# Power.net
KiCad netlist of a schematic drawn in Altium Designer
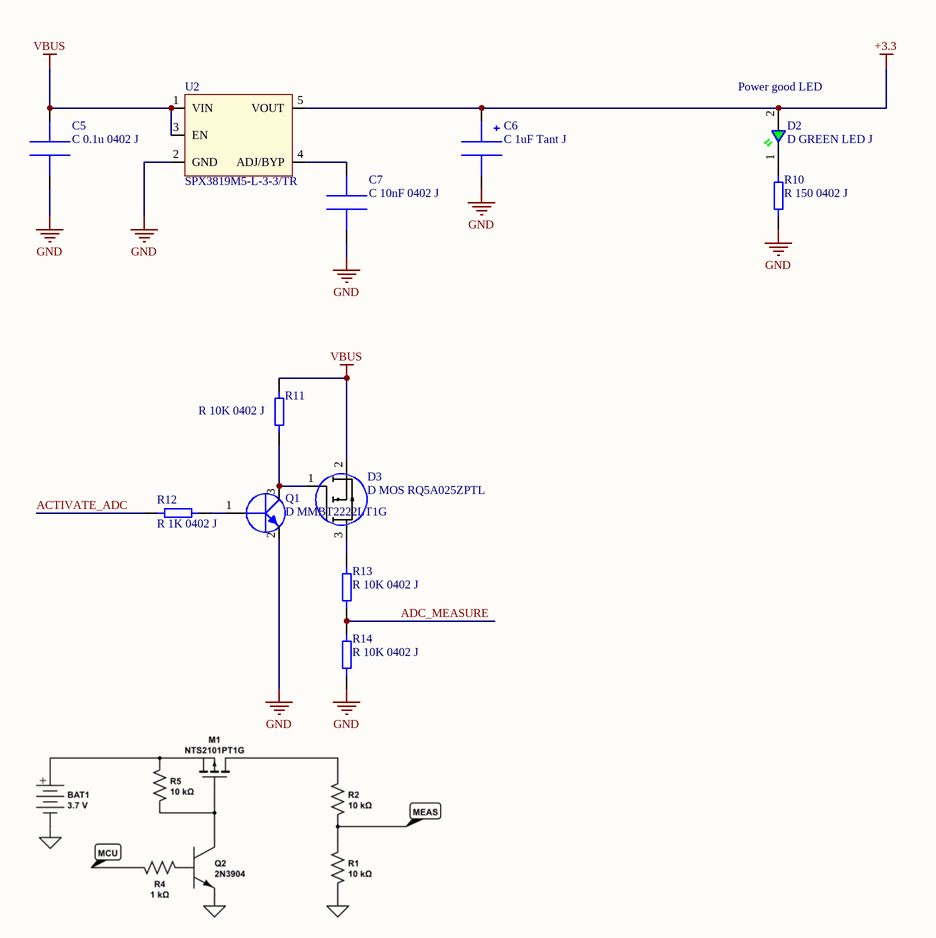
[diagram p0: Power.SchDoc]

(export (version "E")
  (design (tool "Eeschema 10.0.6"))
  (components
    (comp (ref "C5")
      (value "C 0.1u 0402 J")
      (footprint "C0402")
      (description "Cap Ceramic 0.1uF 50V X7R 10% Pad SMD 0402 125C Low ESR Automotive CL05B104KB54PNC")
      (fields
        (field (name "MANUFACTURER") "Samsung")
        (field (name "MANUFACTURER PART NUMBER") "CL05B104KB54PNC")
      )
      (libsource (lib "Schlib1") (part "C 0.1u 0402 J"))
    )
    (comp (ref "C6")
      (value "C 1uF Tant J")
      (footprint "C AVX CAP TANT CASE A")
      (fields
        (field (name "MANUFACTURER") "Kyocera AVX")
        (field (name "MANUFACTURER PART NUMBER") "TAJA105K016RNJ")
        (field (name "TOLERANCE") "20%")
      )
      (libsource (lib "Schlib1") (part "C 1uF Tant J"))
    )
    (comp (ref "C7")
      (value "C 10nF 0402 J")
      (footprint "C0402")
      (description "Ceramic capacitor SMD-0402 10nF /50V X7R# K +-10%, Samsung, RoHS CL05B103KB5NNNC")
      (fields
        (field (name "MANUFACTURER") "Samsung")
        (field (name "MANUFACTURER PART NUMBER") "CL05B103KB5NNNC")
      )
      (libsource (lib "Schlib1") (part "C 10nF 0402 J"))
    )
    (comp (ref "D2")
      (value "D GREEN LED J")
      (footprint "NCD0402C1")
      (description "Green/Yellow-Green 0402 Light Emitting Diodes (LED) ROHS NCD0402C1")
      (fields
        (field (name "MANUFACTURER") "Foshan NationStar Optoelectronics")
        (field (name "MANUFACTURER PART NUMBER") "NCD0402C1")
      )
      (libsource (lib "Schlib1") (part "D GREEN LED J"))
    )
    (comp (ref "D3")
      (value "D MOS RQ5A025ZPTL")
      (footprint "SC96 SOT346T")
      (description "Transistor Mosfet P-ch 12V 2.5A 3-PIN Tsmt T/r")
      (fields (field (name "MANUFACTURER") "Rohm") (field (name "MANUFACTURER PART NUMBER") "RQ5A025ZPTL"))
      (libsource (lib "Schlib1") (part "D MOS RQ5A025ZPTL"))
    )
    (comp (ref "Q1")
      (value "D MMBT2222LT1G")
      (footprint "SOT23")
      (description "Trans GP BJT NPN 30V 0.6A 3-Pin SOT-23 T/R")
      (fields
        (field (name "MANUFACTURER") "ON Semiconductor")
        (field (name "MANUFACTURER PART NUMBER") "MMBT2222LT1G")
      )
      (libsource (lib "Schlib1") (part "D MMBT2222LT1G"))
    )
    (comp (ref "R10")
      (value "R 150 0402 J")
      (footprint "R0402")
      (fields
        (field (name "MANUFACTURER") "Yageo")
        (field (name "MANUFACTURER PART NUMBER") "RC0402FR-07150RL")
        (field (name "TOLERANCE") "1%")
      )
      (libsource (lib "Schlib1") (part "R 150 0402 J"))
    )
    (comp (ref "R11")
      (value "R 10K 0402 J")
      (footprint "R0402")
      (description "Res Thick Film 0402 10K Ohm 1% 0.063W(1/16W) ±100ppm/C Pad SMD Automotive T/R AC0402FR-0710KL")
      (fields
        (field (name "MANUFACTURER") "Yageo")
        (field (name "MANUFACTURER PART NUMBER") "AC0402FR-0710KL")
      )
      (libsource (lib "Schlib1") (part "R 10K 0402 J"))
    )
    (comp (ref "R12")
      (value "R 1K 0402 J")
      (footprint "R0402")
      (description "Res Thick Film 0402 1K Ohm 1% 0.063W(1/16W) ±100ppm/C Pad SMD Automotive T/R")
      (fields
        (field (name "MANUFACTURER") "Yageo")
        (field (name "MANUFACTURER PART NUMBER") "AC0402FR-071KL")
      )
      (libsource (lib "Schlib1") (part "R 1K 0402 J"))
    )
    (comp (ref "R13")
      (value "R 10K 0402 J")
      (footprint "R0402")
      (description "Res Thick Film 0402 10K Ohm 1% 0.063W(1/16W) ±100ppm/C Pad SMD Automotive T/R AC0402FR-0710KL")
      (fields
        (field (name "MANUFACTURER") "Yageo")
        (field (name "MANUFACTURER PART NUMBER") "AC0402FR-0710KL")
      )
      (libsource (lib "Schlib1") (part "R 10K 0402 J"))
    )
    (comp (ref "R14")
      (value "R 10K 0402 J")
      (footprint "R0402")
      (description "Res Thick Film 0402 10K Ohm 1% 0.063W(1/16W) ±100ppm/C Pad SMD Automotive T/R AC0402FR-0710KL")
      (fields
        (field (name "MANUFACTURER") "Yageo")
        (field (name "MANUFACTURER PART NUMBER") "AC0402FR-0710KL")
      )
      (libsource (lib "Schlib1") (part "R 10K 0402 J"))
    )
    (comp (ref "U2")
      (value "SPX3819M5-L-3-3/TR")
      (footprint "SOT23-5")
      (description "SPX3819 Series 3.3 V 500 mA Fixed Output SMT LDO Regulator - SOT-23-5")
      (fields (field (name "MANUFACTURER") "MaxLinear"))
      (libsource (lib "Schlib1") (part "U SPX3819M5 3.3V"))
    )
  )
  (nets
    (net (code "1") (name "+3.3") (class "Default")
      (node (ref "C6") (pin "A") (pinfunction "A_A") (pintype "passive"))
      (node (ref "D2") (pin "2") (pinfunction "2_2") (pintype "passive"))
      (node (ref "U2") (pin "5") (pinfunction "VOUT_5") (pintype "passive"))
    )
    (net (code "2") (name "/ACTIVATE_ADC") (class "Default")
      (node (ref "R12") (pin "1") (pinfunction "1_1") (pintype "passive"))
    )
    (net (code "3") (name "/ADC_MEASURE") (class "Default")
      (node (ref "R13") (pin "1") (pinfunction "1_1") (pintype "passive"))
      (node (ref "R14") (pin "2") (pinfunction "2_2") (pintype "passive"))
    )
    (net (code "4") (name "GND") (class "Default")
      (node (ref "C5") (pin "1") (pinfunction "1_1") (pintype "passive"))
      (node (ref "C6") (pin "K") (pinfunction "K_K") (pintype "passive"))
      (node (ref "C7") (pin "1") (pinfunction "1_1") (pintype "passive"))
      (node (ref "Q1") (pin "2") (pinfunction "2_2") (pintype "passive"))
      (node (ref "R10") (pin "1") (pinfunction "1_1") (pintype "passive"))
      (node (ref "R14") (pin "1") (pinfunction "1_1") (pintype "passive"))
      (node (ref "U2") (pin "2") (pinfunction "GND_2") (pintype "passive"))
    )
    (net (code "5") (name "Net-(D2-Pad1)") (class "Default")
      (node (ref "D2") (pin "1") (pinfunction "1_1") (pintype "passive"))
      (node (ref "R10") (pin "2") (pinfunction "2_2") (pintype "passive"))
    )
    (net (code "6") (name "Net-(D3-D)") (class "Default")
      (node (ref "D3") (pin "3") (pinfunction "D_3") (pintype "passive"))
      (node (ref "R13") (pin "2") (pinfunction "2_2") (pintype "passive"))
    )
    (net (code "7") (name "Net-(D3-G)") (class "Default")
      (node (ref "D3") (pin "1") (pinfunction "G_1") (pintype "passive"))
      (node (ref "Q1") (pin "3") (pinfunction "3_3") (pintype "passive"))
      (node (ref "R11") (pin "1") (pinfunction "1_1") (pintype "passive"))
    )
    (net (code "8") (name "Net-(Q1-Pad1)") (class "Default")
      (node (ref "Q1") (pin "1") (pinfunction "1_1") (pintype "passive"))
      (node (ref "R12") (pin "2") (pinfunction "2_2") (pintype "passive"))
    )
    (net (code "9") (name "Net-(U2-ADJ{slash}BYP)") (class "Default")
      (node (ref "C7") (pin "2") (pinfunction "2_2") (pintype "passive"))
      (node (ref "U2") (pin "4") (pinfunction "ADJ/BYP_4") (pintype "passive"))
    )
    (net (code "10") (name "VBUS") (class "Default")
      (node (ref "C5") (pin "2") (pinfunction "2_2") (pintype "passive"))
      (node (ref "D3") (pin "2") (pinfunction "S_2") (pintype "passive"))
      (node (ref "R11") (pin "2") (pinfunction "2_2") (pintype "passive"))
      (node (ref "U2") (pin "1") (pinfunction "VIN_1") (pintype "passive"))
      (node (ref "U2") (pin "3") (pinfunction "EN_3") (pintype "passive"))
    )
  )
)
